# DM0250_OV9282.net
KiCad netlist of a schematic drawn in Altium Designer
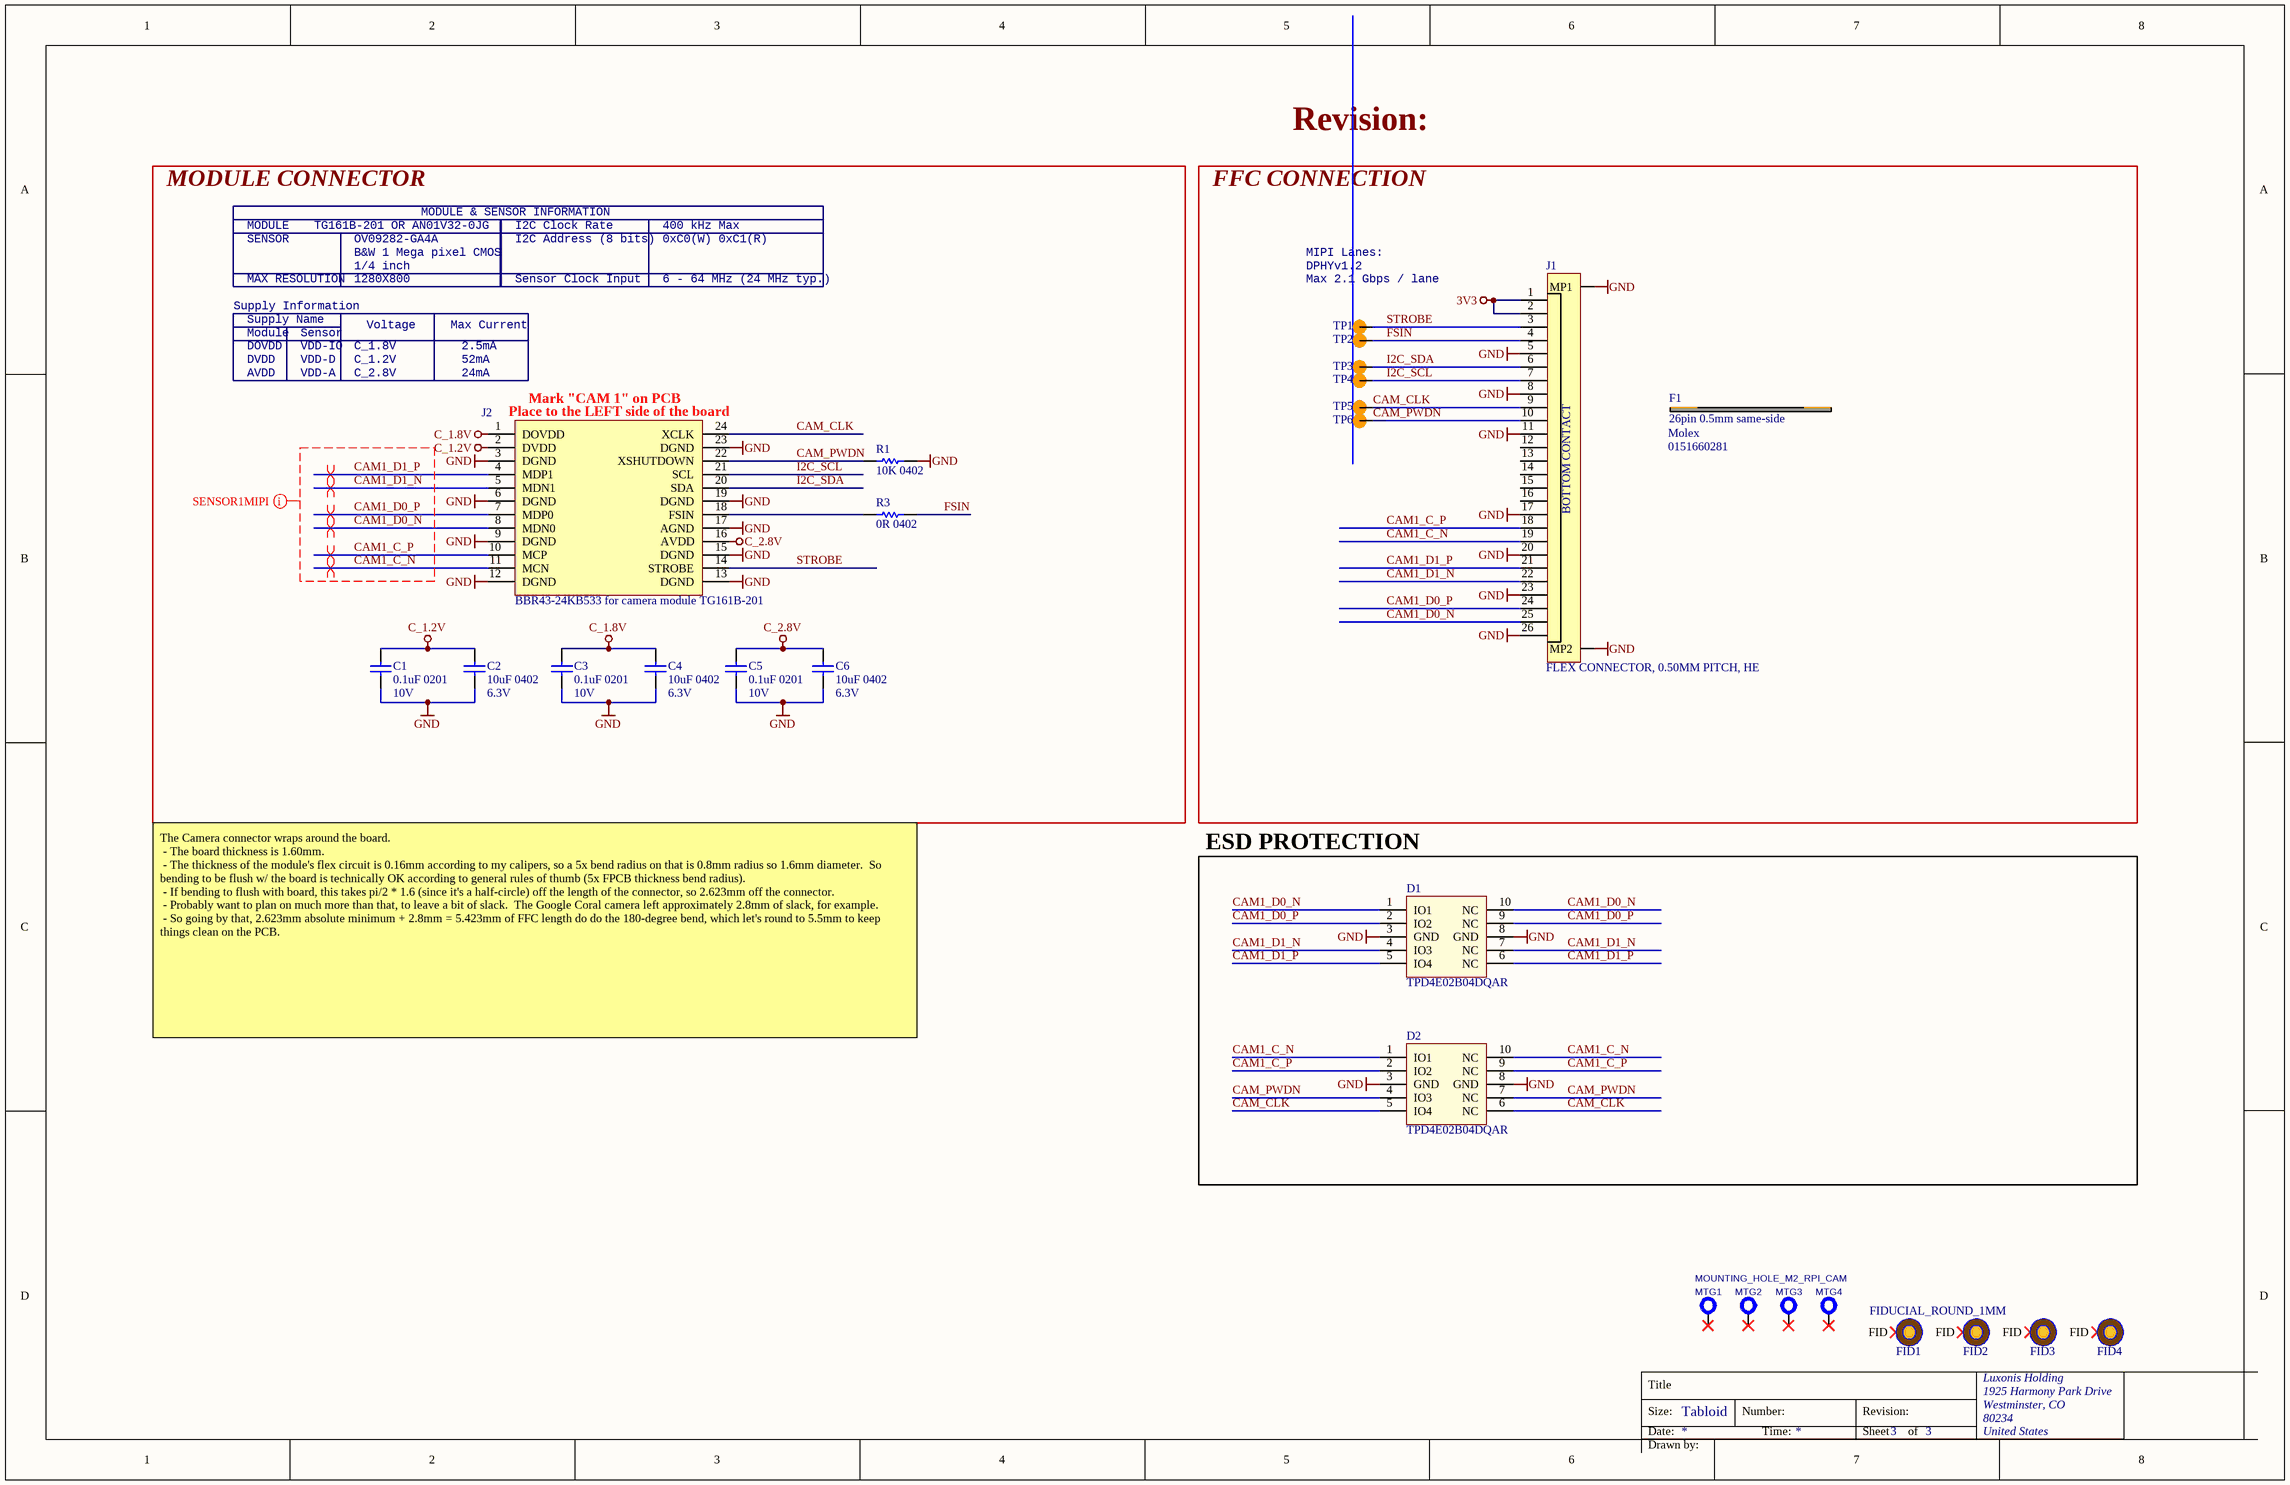
[diagram p0: DM0250_OV9282.SchDoc]

(export (version "E")
  (design (tool "Eeschema 10.0.6"))
  (components
    (comp (ref "C1")
      (value "0.1uF 0201")
      (footprint "CAP_Altium_Vault_Generic:CAPC0201(0603)33_N")
      (description "CAP CER 0.1UF 10V X5R 0201")
      (fields (field (name "TOLERANCE") "10%") (field (name "VOLTAGE") "10V"))
      (libsource (lib "LuxonisMaster") (part "GRM033R61A104KE15D"))
    )
    (comp (ref "C2")
      (value "10uF 0402")
      (footprint "CAP_Altium_Vault_Generic:CAPC0402(1005)70_N")
      (description "CAP CER 10UF 6.3V X5R 0402 20%")
      (fields (field (name "TOLERANCE") "20%") (field (name "VOLTAGE RATING") "6.3V"))
      (libsource (lib "LuxonisMaster") (part "GRM155R60J106ME15D"))
    )
    (comp (ref "C3")
      (value "0.1uF 0201")
      (footprint "CAP_Altium_Vault_Generic:CAPC0201(0603)33_N")
      (description "CAP CER 0.1UF 10V X5R 0201")
      (fields (field (name "TOLERANCE") "10%") (field (name "VOLTAGE") "10V"))
      (libsource (lib "LuxonisMaster") (part "GRM033R61A104KE15D"))
    )
    (comp (ref "C4")
      (value "10uF 0402")
      (footprint "CAP_Altium_Vault_Generic:CAPC0402(1005)70_N")
      (description "CAP CER 10UF 6.3V X5R 0402 20%")
      (fields (field (name "TOLERANCE") "20%") (field (name "VOLTAGE RATING") "6.3V"))
      (libsource (lib "LuxonisMaster") (part "GRM155R60J106ME15D"))
    )
    (comp (ref "C5")
      (value "0.1uF 0201")
      (footprint "CAP_Altium_Vault_Generic:CAPC0201(0603)33_N")
      (description "CAP CER 0.1UF 10V X5R 0201")
      (fields (field (name "TOLERANCE") "10%") (field (name "VOLTAGE") "10V"))
      (libsource (lib "LuxonisMaster") (part "GRM033R61A104KE15D"))
    )
    (comp (ref "C6")
      (value "10uF 0402")
      (footprint "CAP_Altium_Vault_Generic:CAPC0402(1005)70_N")
      (description "CAP CER 10UF 6.3V X5R 0402 20%")
      (fields (field (name "TOLERANCE") "20%") (field (name "VOLTAGE RATING") "6.3V"))
      (libsource (lib "LuxonisMaster") (part "GRM155R60J106ME15D"))
    )
    (comp (ref "D1")
      (value "TPD4E02B04DQAR")
      (footprint "LuxonisMaster:TPD4E02B04DQAR")
      (libsource (lib "LuxonisMaster") (part "TPD4E02B04DQAR"))
    )
    (comp (ref "D2")
      (value "TPD4E02B04DQAR")
      (footprint "LuxonisMaster:TPD4E02B04DQAR")
      (libsource (lib "LuxonisMaster") (part "TPD4E02B04DQAR"))
    )
    (comp (ref "F1")
      (value "26pin 0.5mm same-side")
      (description "CABLE FFC 26POS 0.50MM 6\"")
      (fields
        (field (name "MANUFACTURER 1") "Molex")
        (field (name "MANUFACTURER PART NUMBER 1") "0151660281")
      )
      (libsource (lib "BG0249_R1M1E1") (part "0151660281"))
    )
    (comp (ref "FID1")
      (value "FIDUCIAL_ROUND_1MM")
      (footprint "LuxonisMaster:FIDUCIAL_ROUND_1MM")
      (description "Fiducial with various available footprints")
      (libsource (lib "LuxonisMaster") (part "FIDUCIAL"))
    )
    (comp (ref "FID2")
      (value "FIDUCIAL_ROUND_1MM")
      (footprint "LuxonisMaster:FIDUCIAL_ROUND_1MM")
      (description "Fiducial with various available footprints")
      (libsource (lib "LuxonisMaster") (part "FIDUCIAL"))
    )
    (comp (ref "FID3")
      (value "FIDUCIAL_ROUND_1MM")
      (footprint "LuxonisMaster:FIDUCIAL_ROUND_1MM")
      (description "Fiducial with various available footprints")
      (libsource (lib "LuxonisMaster") (part "FIDUCIAL"))
    )
    (comp (ref "FID4")
      (value "FIDUCIAL_ROUND_1MM")
      (footprint "LuxonisMaster:FIDUCIAL_ROUND_1MM")
      (description "Fiducial with various available footprints")
      (libsource (lib "LuxonisMaster") (part "FIDUCIAL"))
    )
    (comp (ref "J1")
      (value "FLEX CONNECTOR, 0.50MM PITCH, HE")
      (footprint "DM1090FFC:F32R-1A7H1-11026")
      (description "26 Position FFC, FPC Connector Contacts, Bottom 0.020\" (0.50mm) Surface Mount, Right Angle")
      (libsource (lib "DM1090FFC") (part "F32R-1A7H1-11026"))
    )
    (comp (ref "J2")
      (value "BBR43-24KB533 for camera module TG161B-201")
      (footprint "DM1090FFC:TG161B-201 / AN01V32 - Board Wrap")
      (description "CONN 24 way, 2 row board to board connector SMD")
      (libsource (lib "DM1090FFC") (part "TG161B-201_Connector"))
    )
    (comp (ref "MTG1")
      (value "MOUNTING_HOLE_M2_RPI_CAM")
      (footprint "LuxonisMaster:MOUNTING_HOLE_M2_RPI_CAM")
      (description "=CurrentFootprint")
      (libsource (lib "LuxonisMaster") (part "MP_Mounting-Holes"))
    )
    (comp (ref "MTG2")
      (value "MOUNTING_HOLE_M2_RPI_CAM")
      (footprint "LuxonisMaster:MOUNTING_HOLE_M2_RPI_CAM")
      (description "=CurrentFootprint")
      (libsource (lib "LuxonisMaster") (part "MP_Mounting-Holes"))
    )
    (comp (ref "MTG3")
      (value "MOUNTING_HOLE_M2_RPI_CAM")
      (footprint "LuxonisMaster:MOUNTING_HOLE_M2_RPI_CAM")
      (description "=CurrentFootprint")
      (libsource (lib "LuxonisMaster") (part "MP_Mounting-Holes"))
    )
    (comp (ref "MTG4")
      (value "MOUNTING_HOLE_M2_RPI_CAM")
      (footprint "LuxonisMaster:MOUNTING_HOLE_M2_RPI_CAM")
      (description "=CurrentFootprint")
      (libsource (lib "LuxonisMaster") (part "MP_Mounting-Holes"))
    )
    (comp (ref "R1")
      (value "10K 0402")
      (footprint "RES_Altium_Vault_Generic:RESC0402(1005)_N")
      (fields (field (name "TOLERANCE") "1%"))
      (libsource (lib "LuxonisMaster") (part "RC0402FR-1310KL"))
    )
    (comp (ref "R3")
      (value "0R 0402")
      (footprint "RES_Altium_Vault_Generic:RESC0402(1005)_L")
      (description "RES SMD 0 OHM JUMPER 1/16W 0402")
      (fields (field (name "TOLERANCE") "5%"))
      (libsource (lib "LuxonisMaster") (part "CRCW04020000Z0ED"))
    )
    (comp (ref "TP1")
      (value "TP100_150_NS")
      (footprint "LuxonisMaster:TP100_150_NS")
      (libsource (lib "LuxonisMaster") (part "TEST_POINT"))
    )
    (comp (ref "TP2")
      (value "TP100_150_NS")
      (footprint "LuxonisMaster:TP100_150_NS")
      (libsource (lib "LuxonisMaster") (part "TEST_POINT"))
    )
    (comp (ref "TP3")
      (value "TP100_150_NS")
      (footprint "LuxonisMaster:TP100_150_NS")
      (libsource (lib "LuxonisMaster") (part "TEST_POINT"))
    )
    (comp (ref "TP4")
      (value "TP100_150_NS")
      (footprint "LuxonisMaster:TP100_150_NS")
      (libsource (lib "LuxonisMaster") (part "TEST_POINT"))
    )
    (comp (ref "TP5")
      (value "TP100_150_NS")
      (footprint "LuxonisMaster:TP100_150_NS")
      (libsource (lib "LuxonisMaster") (part "TEST_POINT"))
    )
    (comp (ref "TP6")
      (value "TP100_150_NS")
      (footprint "LuxonisMaster:TP100_150_NS")
      (libsource (lib "LuxonisMaster") (part "TEST_POINT"))
    )
  )
  (nets
    (net (code "1") (name "/CAM1_C_N") (class "Default")
      (node (ref "D2") (pin "1") (pinfunction "IO1_1") (pintype "passive"))
      (node (ref "D2") (pin "10") (pinfunction "NC_10") (pintype "passive"))
      (node (ref "J1") (pin "19") (pinfunction "19_19") (pintype "passive"))
      (node (ref "J2") (pin "11") (pinfunction "MCN_11") (pintype "passive"))
    )
    (net (code "2") (name "/CAM1_C_P") (class "Default")
      (node (ref "D2") (pin "2") (pinfunction "IO2_2") (pintype "passive"))
      (node (ref "D2") (pin "9") (pinfunction "NC_9") (pintype "passive"))
      (node (ref "J1") (pin "18") (pinfunction "18_18") (pintype "passive"))
      (node (ref "J2") (pin "10") (pinfunction "MCP_10") (pintype "passive"))
    )
    (net (code "3") (name "/CAM1_D0_N") (class "Default")
      (node (ref "D1") (pin "1") (pinfunction "IO1_1") (pintype "passive"))
      (node (ref "D1") (pin "10") (pinfunction "NC_10") (pintype "passive"))
      (node (ref "J1") (pin "25") (pinfunction "25_25") (pintype "passive"))
      (node (ref "J2") (pin "8") (pinfunction "MDN0_8") (pintype "passive"))
    )
    (net (code "4") (name "/CAM1_D0_P") (class "Default")
      (node (ref "D1") (pin "2") (pinfunction "IO2_2") (pintype "passive"))
      (node (ref "D1") (pin "9") (pinfunction "NC_9") (pintype "passive"))
      (node (ref "J1") (pin "24") (pinfunction "24_24") (pintype "passive"))
      (node (ref "J2") (pin "7") (pinfunction "MDP0_7") (pintype "passive"))
    )
    (net (code "5") (name "/CAM1_D1_N") (class "Default")
      (node (ref "D1") (pin "4") (pinfunction "IO3_4") (pintype "passive"))
      (node (ref "D1") (pin "7") (pinfunction "NC_7") (pintype "passive"))
      (node (ref "J1") (pin "22") (pinfunction "22_22") (pintype "passive"))
      (node (ref "J2") (pin "5") (pinfunction "MDN1_5") (pintype "passive"))
    )
    (net (code "6") (name "/CAM1_D1_P") (class "Default")
      (node (ref "D1") (pin "5") (pinfunction "IO4_5") (pintype "passive"))
      (node (ref "D1") (pin "6") (pinfunction "NC_6") (pintype "passive"))
      (node (ref "J1") (pin "21") (pinfunction "21_21") (pintype "passive"))
      (node (ref "J2") (pin "4") (pinfunction "MDP1_4") (pintype "passive"))
    )
    (net (code "7") (name "/CAM_CLK") (class "Default")
      (node (ref "D2") (pin "5") (pinfunction "IO4_5") (pintype "passive"))
      (node (ref "D2") (pin "6") (pinfunction "NC_6") (pintype "passive"))
      (node (ref "J1") (pin "9") (pinfunction "9_9") (pintype "passive"))
      (node (ref "J2") (pin "24") (pinfunction "XCLK_24") (pintype "passive"))
      (node (ref "TP5") (pin "1") (pintype "passive"))
    )
    (net (code "8") (name "/CAM_PWDN") (class "Default")
      (node (ref "D2") (pin "4") (pinfunction "IO3_4") (pintype "passive"))
      (node (ref "D2") (pin "7") (pinfunction "NC_7") (pintype "passive"))
      (node (ref "J1") (pin "10") (pinfunction "10_10") (pintype "passive"))
      (node (ref "J2") (pin "22") (pinfunction "XSHUTDOWN_22") (pintype "passive"))
      (node (ref "R1") (pin "1") (pinfunction "1_1") (pintype "passive"))
      (node (ref "TP6") (pin "1") (pintype "passive"))
    )
    (net (code "9") (name "/FSIN") (class "Default")
      (node (ref "J1") (pin "4") (pinfunction "4_4") (pintype "passive"))
      (node (ref "R3") (pin "2") (pinfunction "2_2") (pintype "passive"))
      (node (ref "TP2") (pin "1") (pintype "passive"))
    )
    (net (code "10") (name "/I2C_SCL") (class "Default")
      (node (ref "J1") (pin "7") (pinfunction "7_7") (pintype "passive"))
      (node (ref "J2") (pin "21") (pinfunction "SCL_21") (pintype "passive"))
      (node (ref "TP4") (pin "1") (pintype "passive"))
    )
    (net (code "11") (name "/I2C_SDA") (class "Default")
      (node (ref "J1") (pin "6") (pinfunction "6_6") (pintype "passive"))
      (node (ref "J2") (pin "20") (pinfunction "SDA_20") (pintype "passive"))
      (node (ref "TP3") (pin "1") (pintype "passive"))
    )
    (net (code "12") (name "/STROBE") (class "Default")
      (node (ref "J1") (pin "3") (pinfunction "3_3") (pintype "passive"))
      (node (ref "J2") (pin "14") (pinfunction "STROBE_14") (pintype "passive"))
      (node (ref "TP1") (pin "1") (pintype "passive"))
    )
    (net (code "13") (name "3V3") (class "Default")
      (node (ref "J1") (pin "1") (pinfunction "1_1") (pintype "passive"))
      (node (ref "J1") (pin "2") (pinfunction "2_2") (pintype "passive"))
    )
    (net (code "14") (name "C_1.2V") (class "Default")
      (node (ref "C1") (pin "2") (pinfunction "2_2") (pintype "passive"))
      (node (ref "C2") (pin "2") (pinfunction "2_2") (pintype "passive"))
      (node (ref "J2") (pin "2") (pinfunction "DVDD_2") (pintype "passive"))
    )
    (net (code "15") (name "C_1.8V") (class "Default")
      (node (ref "C3") (pin "2") (pinfunction "2_2") (pintype "passive"))
      (node (ref "C4") (pin "2") (pinfunction "2_2") (pintype "passive"))
      (node (ref "J2") (pin "1") (pinfunction "DOVDD_1") (pintype "passive"))
    )
    (net (code "16") (name "C_2.8V") (class "Default")
      (node (ref "C5") (pin "2") (pinfunction "2_2") (pintype "passive"))
      (node (ref "C6") (pin "2") (pinfunction "2_2") (pintype "passive"))
      (node (ref "J2") (pin "16") (pinfunction "AVDD_16") (pintype "passive"))
    )
    (net (code "17") (name "GND") (class "Default")
      (node (ref "C1") (pin "1") (pinfunction "1_1") (pintype "passive"))
      (node (ref "C2") (pin "1") (pinfunction "1_1") (pintype "passive"))
      (node (ref "C3") (pin "1") (pinfunction "1_1") (pintype "passive"))
      (node (ref "C4") (pin "1") (pinfunction "1_1") (pintype "passive"))
      (node (ref "C5") (pin "1") (pinfunction "1_1") (pintype "passive"))
      (node (ref "C6") (pin "1") (pinfunction "1_1") (pintype "passive"))
      (node (ref "D1") (pin "3") (pinfunction "GND_3") (pintype "passive"))
      (node (ref "D1") (pin "8") (pinfunction "GND_8") (pintype "passive"))
      (node (ref "D2") (pin "3") (pinfunction "GND_3") (pintype "passive"))
      (node (ref "D2") (pin "8") (pinfunction "GND_8") (pintype "passive"))
      (node (ref "J1") (pin "11") (pinfunction "11_11") (pintype "passive"))
      (node (ref "J1") (pin "17") (pinfunction "17_17") (pintype "passive"))
      (node (ref "J1") (pin "20") (pinfunction "20_20") (pintype "passive"))
      (node (ref "J1") (pin "23") (pinfunction "23_23") (pintype "passive"))
      (node (ref "J1") (pin "26") (pinfunction "26_26") (pintype "passive"))
      (node (ref "J1") (pin "5") (pinfunction "5_5") (pintype "passive"))
      (node (ref "J1") (pin "8") (pinfunction "8_8") (pintype "passive"))
      (node (ref "J1") (pin "MP1") (pinfunction "MP1_MP1") (pintype "passive"))
      (node (ref "J1") (pin "MP2") (pinfunction "MP2_MP2") (pintype "passive"))
      (node (ref "J2") (pin "12") (pinfunction "DGND_12") (pintype "passive"))
      (node (ref "J2") (pin "13") (pinfunction "DGND_13") (pintype "passive"))
      (node (ref "J2") (pin "15") (pinfunction "DGND_15") (pintype "passive"))
      (node (ref "J2") (pin "17") (pinfunction "AGND_17") (pintype "passive"))
      (node (ref "J2") (pin "19") (pinfunction "DGND_19") (pintype "passive"))
      (node (ref "J2") (pin "23") (pinfunction "DGND_23") (pintype "passive"))
      (node (ref "J2") (pin "3") (pinfunction "DGND_3") (pintype "passive"))
      (node (ref "J2") (pin "6") (pinfunction "DGND_6") (pintype "passive"))
      (node (ref "J2") (pin "9") (pinfunction "DGND_9") (pintype "passive"))
      (node (ref "R1") (pin "2") (pinfunction "2_2") (pintype "passive"))
    )
    (net (code "18") (name "Net-(J2-FSIN)") (class "Default")
      (node (ref "J2") (pin "18") (pinfunction "FSIN_18") (pintype "passive"))
      (node (ref "R3") (pin "1") (pinfunction "1_1") (pintype "passive"))
    )
    (net (code "19") (name "unconnected-(FID1-PadFID)") (class "Default")
      (node (ref "FID1") (pin "FID") (pinfunction "FID_FID") (pintype "input+no_connect"))
    )
    (net (code "20") (name "unconnected-(FID2-PadFID)") (class "Default")
      (node (ref "FID2") (pin "FID") (pinfunction "FID_FID") (pintype "input+no_connect"))
    )
    (net (code "21") (name "unconnected-(FID3-PadFID)") (class "Default")
      (node (ref "FID3") (pin "FID") (pinfunction "FID_FID") (pintype "input+no_connect"))
    )
    (net (code "22") (name "unconnected-(FID4-PadFID)") (class "Default")
      (node (ref "FID4") (pin "FID") (pinfunction "FID_FID") (pintype "input+no_connect"))
    )
    (net (code "23") (name "unconnected-(J1-Pad12)") (class "Default")
      (node (ref "J1") (pin "12") (pinfunction "12_12") (pintype "passive"))
    )
    (net (code "24") (name "unconnected-(J1-Pad13)") (class "Default")
      (node (ref "J1") (pin "13") (pinfunction "13_13") (pintype "passive"))
    )
    (net (code "25") (name "unconnected-(J1-Pad14)") (class "Default")
      (node (ref "J1") (pin "14") (pinfunction "14_14") (pintype "passive"))
    )
    (net (code "26") (name "unconnected-(J1-Pad15)") (class "Default")
      (node (ref "J1") (pin "15") (pinfunction "15_15") (pintype "passive"))
    )
    (net (code "27") (name "unconnected-(J1-Pad16)") (class "Default")
      (node (ref "J1") (pin "16") (pinfunction "16_16") (pintype "passive"))
    )
    (net (code "28") (name "unconnected-(MTG1-Pad1)") (class "Default")
      (node (ref "MTG1") (pin "1") (pintype "passive+no_connect"))
    )
    (net (code "29") (name "unconnected-(MTG2-Pad1)") (class "Default")
      (node (ref "MTG2") (pin "1") (pintype "passive+no_connect"))
    )
    (net (code "30") (name "unconnected-(MTG3-Pad1)") (class "Default")
      (node (ref "MTG3") (pin "1") (pintype "passive+no_connect"))
    )
    (net (code "31") (name "unconnected-(MTG4-Pad1)") (class "Default")
      (node (ref "MTG4") (pin "1") (pintype "passive+no_connect"))
    )
  )
)
